# ipmi.net
KiCad netlist of a schematic drawn in Altium Designer
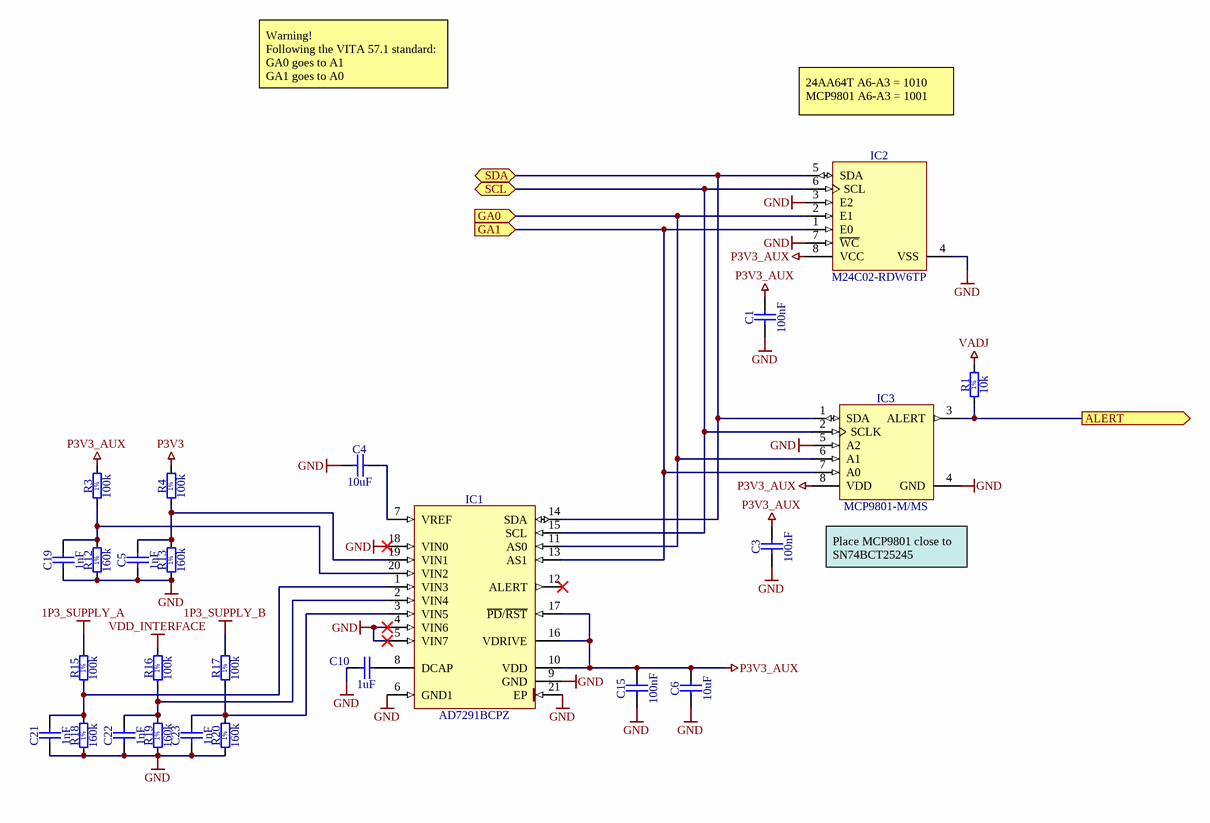
[diagram p0: ipmi.SchDoc]

(export (version "E")
  (design (tool "Eeschema 10.0.6"))
  (components
    (comp (ref "C1")
      (value "100nF")
      (footprint "CAPC1005X55N")
      (description "Non-polarised capacitor")
      (fields
        (field (name "PART NUMBER") "CC0402_100NF_16V_10%_X7R")
        (field (name "VOLTAGE") "16V")
        (field (name "AUTHOR") "CERN DEM JLC")
      )
      (libsource (lib "Capacitors") (part "Capacitor - non polarized"))
    )
    (comp (ref "C3")
      (value "100nF")
      (footprint "CAPC1005X55N")
      (description "Non-polarised capacitor")
      (fields
        (field (name "PART NUMBER") "CC0402_100NF_16V_10%_X7R")
        (field (name "VOLTAGE") "16V")
        (field (name "AUTHOR") "CERN DEM JLC")
      )
      (libsource (lib "Capacitors") (part "Capacitor - non polarized"))
    )
    (comp (ref "C4")
      (value "10uF")
      (footprint "CAPC1608X87N")
      (description "Non-polarised capacitor")
      (fields
        (field (name "PART NUMBER") "CC0603_10UF_6.3V_20%_X5R")
        (field (name "VOLTAGE") "6.3V")
        (field (name "AUTHOR") "CERN DEM JLC")
      )
      (libsource (lib "Capacitors") (part "Capacitor - non polarized"))
    )
    (comp (ref "C5")
      (value "1nF")
      (footprint "CAPC1005X55N")
      (description "Non-polarised capacitor")
      (fields
        (field (name "PART NUMBER") "CC0402_1NF_50V_10%_X7R")
        (field (name "VOLTAGE") "50V")
        (field (name "AUTHOR") "CERN DEM JLC")
      )
      (libsource (lib "Capacitors") (part "Capacitor - non polarized"))
    )
    (comp (ref "C6")
      (value "10uF")
      (footprint "CAPC1608X87N")
      (description "Non-polarised capacitor")
      (fields
        (field (name "PART NUMBER") "CC0603_10UF_6.3V_20%_X5R")
        (field (name "VOLTAGE") "6.3V")
        (field (name "AUTHOR") "CERN DEM JLC")
      )
      (libsource (lib "Capacitors") (part "Capacitor - non polarized"))
    )
    (comp (ref "C10")
      (value "1uF")
      (footprint "CAPC1608X87N")
      (description "Non-polarised capacitor")
      (fields
        (field (name "PART NUMBER") "CC0603_1UF_16V_10%_X7R")
        (field (name "VOLTAGE") "16V")
        (field (name "AUTHOR") "CERN DEM JLC")
      )
      (libsource (lib "Capacitors") (part "Capacitor - non polarized"))
    )
    (comp (ref "C15")
      (value "100nF")
      (footprint "CAPC1005X55N")
      (description "Non-polarised capacitor")
      (fields
        (field (name "PART NUMBER") "CC0402_100NF_16V_10%_X7R")
        (field (name "VOLTAGE") "16V")
        (field (name "AUTHOR") "CERN DEM JLC")
      )
      (libsource (lib "Capacitors") (part "Capacitor - non polarized"))
    )
    (comp (ref "C19")
      (value "1nF")
      (footprint "CAPC1005X55N")
      (description "Non-polarised capacitor")
      (fields
        (field (name "PART NUMBER") "CC0402_1NF_50V_10%_X7R")
        (field (name "VOLTAGE") "50V")
        (field (name "AUTHOR") "CERN DEM JLC")
      )
      (libsource (lib "Capacitors") (part "Capacitor - non polarized"))
    )
    (comp (ref "C21")
      (value "1nF")
      (footprint "CAPC1005X55N")
      (description "Non-polarised capacitor")
      (fields
        (field (name "PART NUMBER") "CC0402_1NF_50V_10%_X7R")
        (field (name "VOLTAGE") "50V")
        (field (name "AUTHOR") "CERN DEM JLC")
      )
      (libsource (lib "Capacitors") (part "Capacitor - non polarized"))
    )
    (comp (ref "C22")
      (value "1nF")
      (footprint "CAPC1005X55N")
      (description "Non-polarised capacitor")
      (fields
        (field (name "PART NUMBER") "CC0402_1NF_50V_10%_X7R")
        (field (name "VOLTAGE") "50V")
        (field (name "AUTHOR") "CERN DEM JLC")
      )
      (libsource (lib "Capacitors") (part "Capacitor - non polarized"))
    )
    (comp (ref "C23")
      (value "1nF")
      (footprint "CAPC1005X55N")
      (description "Non-polarised capacitor")
      (fields
        (field (name "PART NUMBER") "CC0402_1NF_50V_10%_X7R")
        (field (name "VOLTAGE") "50V")
        (field (name "AUTHOR") "CERN DEM JLC")
      )
      (libsource (lib "Capacitors") (part "Capacitor - non polarized"))
    )
    (comp (ref "IC1")
      (value "AD7291BCPZ")
      (footprint "QFN50P400X400X80-21N-S275")
      (description "8-Channel, I2C, 12-Bit SAR ADC with Temperature Sensor")
      (fields (field (name "MANUFACTURER") "ANALOG DEVICES") (field (name "AUTHOR") "CERN DEM JLC"))
      (libsource (lib "ICs And Semiconductors") (part "AD7291"))
    )
    (comp (ref "IC2")
      (value "M24C02-RDW6TP")
      (footprint "SOP65P640X120-8N")
      (description "2-Kbit (256 x 8bit) Serial I2C Bus EEPROM")
      (fields (field (name "MANUFACTURER") "ST MICROELECTRONICS") (field (name "AUTHOR") "CERN DEM JLC"))
      (libsource (lib "ICs And Semiconductors") (part "M24C02‐RDW"))
    )
    (comp (ref "IC3")
      (value "MCP9801-M/MS")
      (footprint "SOP65P490X110-8N")
      (description "2-Wire High-Accuracy Temperature Sensor")
      (fields (field (name "MANUFACTURER") "MICROCHIP TECHNOLOGIY") (field (name "AUTHOR") "CERN DEM JLC"))
      (libsource (lib "ICs And Semiconductors") (part "MCP9801-M/MS"))
    )
    (comp (ref "R1")
      (value "10k")
      (footprint "RESC1005X40N")
      (description "Resistor - 1%")
      (fields
        (field (name "PART NUMBER") "R0402_10K_1%_0.0625W_100PPM")
        (field (name "POWER") "0.0625W")
        (field (name "AUTHOR") "CERN DEM JLC")
      )
      (libsource (lib "Resistors") (part "Resistor - 1%"))
    )
    (comp (ref "R3")
      (value "100k")
      (footprint "RESC1005X40N")
      (description "Resistor - 1%")
      (fields
        (field (name "PART NUMBER") "R0402_100K_1%_0.0625W_100PPM")
        (field (name "POWER") "0.0625W")
        (field (name "AUTHOR") "CERN DEM JLC")
      )
      (libsource (lib "Resistors") (part "Resistor - 1%"))
    )
    (comp (ref "R4")
      (value "100k")
      (footprint "RESC1005X40N")
      (description "Resistor - 1%")
      (fields
        (field (name "PART NUMBER") "R0402_100K_1%_0.0625W_100PPM")
        (field (name "POWER") "0.0625W")
        (field (name "AUTHOR") "CERN DEM JLC")
      )
      (libsource (lib "Resistors") (part "Resistor - 1%"))
    )
    (comp (ref "R12")
      (value "160k")
      (footprint "RESC1005X40N")
      (description "Resistor - 1%")
      (fields
        (field (name "PART NUMBER") "R0402_160K_1%_0.0625W_100PPM")
        (field (name "POWER") "0.0625W")
        (field (name "AUTHOR") "CERN DEM JLC")
      )
      (libsource (lib "Resistors") (part "Resistor - 1%"))
    )
    (comp (ref "R13")
      (value "160k")
      (footprint "RESC1005X40N")
      (description "Resistor - 1%")
      (fields
        (field (name "PART NUMBER") "R0402_160K_1%_0.0625W_100PPM")
        (field (name "POWER") "0.0625W")
        (field (name "AUTHOR") "CERN DEM JLC")
      )
      (libsource (lib "Resistors") (part "Resistor - 1%"))
    )
    (comp (ref "R15")
      (value "100k")
      (footprint "RESC1005X40N")
      (description "Resistor - 1%")
      (fields
        (field (name "PART NUMBER") "R0402_100K_1%_0.0625W_100PPM")
        (field (name "POWER") "0.0625W")
        (field (name "AUTHOR") "CERN DEM JLC")
      )
      (libsource (lib "Resistors") (part "Resistor - 1%"))
    )
    (comp (ref "R16")
      (value "100k")
      (footprint "RESC1005X40N")
      (description "Resistor - 1%")
      (fields
        (field (name "PART NUMBER") "R0402_100K_1%_0.0625W_100PPM")
        (field (name "POWER") "0.0625W")
        (field (name "AUTHOR") "CERN DEM JLC")
      )
      (libsource (lib "Resistors") (part "Resistor - 1%"))
    )
    (comp (ref "R17")
      (value "100k")
      (footprint "RESC1005X40N")
      (description "Resistor - 1%")
      (fields
        (field (name "PART NUMBER") "R0402_100K_1%_0.0625W_100PPM")
        (field (name "POWER") "0.0625W")
        (field (name "AUTHOR") "CERN DEM JLC")
      )
      (libsource (lib "Resistors") (part "Resistor - 1%"))
    )
    (comp (ref "R18")
      (value "160k")
      (footprint "RESC1005X40N")
      (description "Resistor - 1%")
      (fields
        (field (name "PART NUMBER") "R0402_160K_1%_0.0625W_100PPM")
        (field (name "POWER") "0.0625W")
        (field (name "AUTHOR") "CERN DEM JLC")
      )
      (libsource (lib "Resistors") (part "Resistor - 1%"))
    )
    (comp (ref "R19")
      (value "160k")
      (footprint "RESC1005X40N")
      (description "Resistor - 1%")
      (fields
        (field (name "PART NUMBER") "R0402_160K_1%_0.0625W_100PPM")
        (field (name "POWER") "0.0625W")
        (field (name "AUTHOR") "CERN DEM JLC")
      )
      (libsource (lib "Resistors") (part "Resistor - 1%"))
    )
    (comp (ref "R20")
      (value "160k")
      (footprint "RESC1005X40N")
      (description "Resistor - 1%")
      (fields
        (field (name "PART NUMBER") "R0402_160K_1%_0.0625W_100PPM")
        (field (name "POWER") "0.0625W")
        (field (name "AUTHOR") "CERN DEM JLC")
      )
      (libsource (lib "Resistors") (part "Resistor - 1%"))
    )
  )
  (nets
    (net (code "1") (name "/ALERT") (class "Default")
      (node (ref "IC3") (pin "3") (pinfunction "ALERT_3") (pintype "output"))
      (node (ref "R1") (pin "1") (pinfunction "1_1") (pintype "passive"))
    )
    (net (code "2") (name "/GA0") (class "Default")
      (node (ref "IC1") (pin "11") (pinfunction "AS0_11") (pintype "input"))
      (node (ref "IC2") (pin "2") (pinfunction "E1_2") (pintype "input"))
      (node (ref "IC3") (pin "6") (pinfunction "A1_6") (pintype "input"))
    )
    (net (code "3") (name "/GA1") (class "Default")
      (node (ref "IC1") (pin "13") (pinfunction "AS1_13") (pintype "input"))
      (node (ref "IC2") (pin "1") (pinfunction "E0_1") (pintype "input"))
      (node (ref "IC3") (pin "7") (pinfunction "A0_7") (pintype "input"))
    )
    (net (code "4") (name "/SCL") (class "Default")
      (node (ref "IC1") (pin "15") (pinfunction "SCL_15") (pintype "input"))
      (node (ref "IC2") (pin "6") (pinfunction "SCL_6") (pintype "input"))
      (node (ref "IC3") (pin "2") (pinfunction "SCLK_2") (pintype "input"))
    )
    (net (code "5") (name "/SDA") (class "Default")
      (node (ref "IC1") (pin "14") (pinfunction "SDA_14") (pintype "bidirectional"))
      (node (ref "IC2") (pin "5") (pinfunction "SDA_5") (pintype "bidirectional"))
      (node (ref "IC3") (pin "1") (pinfunction "SDA_1") (pintype "bidirectional"))
    )
    (net (code "6") (name "1P3_SUPPLY_A") (class "Default")
      (node (ref "R15") (pin "2") (pinfunction "2_2") (pintype "passive"))
    )
    (net (code "7") (name "1P3_SUPPLY_B") (class "Default")
      (node (ref "R17") (pin "2") (pinfunction "2_2") (pintype "passive"))
    )
    (net (code "8") (name "GND") (class "Default")
      (node (ref "C1") (pin "1") (pinfunction "1_1") (pintype "passive"))
      (node (ref "C10") (pin "1") (pinfunction "1_1") (pintype "passive"))
      (node (ref "C15") (pin "1") (pinfunction "1_1") (pintype "passive"))
      (node (ref "C19") (pin "1") (pinfunction "1_1") (pintype "passive"))
      (node (ref "C21") (pin "1") (pinfunction "1_1") (pintype "passive"))
      (node (ref "C22") (pin "1") (pinfunction "1_1") (pintype "passive"))
      (node (ref "C23") (pin "1") (pinfunction "1_1") (pintype "passive"))
      (node (ref "C3") (pin "1") (pinfunction "1_1") (pintype "passive"))
      (node (ref "C4") (pin "1") (pinfunction "1_1") (pintype "passive"))
      (node (ref "C5") (pin "1") (pinfunction "1_1") (pintype "passive"))
      (node (ref "C6") (pin "1") (pinfunction "1_1") (pintype "passive"))
      (node (ref "IC1") (pin "18") (pinfunction "VIN0_18") (pintype "input"))
      (node (ref "IC1") (pin "21") (pinfunction "EP_21") (pintype "input"))
      (node (ref "IC1") (pin "4") (pinfunction "VIN6_4") (pintype "input"))
      (node (ref "IC1") (pin "5") (pinfunction "VIN7_5") (pintype "input"))
      (node (ref "IC1") (pin "6") (pinfunction "GND1_6") (pintype "input"))
      (node (ref "IC1") (pin "9") (pinfunction "GND_9") (pintype "power_in"))
      (node (ref "IC2") (pin "3") (pinfunction "E2_3") (pintype "input"))
      (node (ref "IC2") (pin "4") (pinfunction "VSS_4") (pintype "power_in"))
      (node (ref "IC2") (pin "7") (pinfunction "~{WC}_7") (pintype "input"))
      (node (ref "IC3") (pin "4") (pinfunction "GND_4") (pintype "power_in"))
      (node (ref "IC3") (pin "5") (pinfunction "A2_5") (pintype "input"))
      (node (ref "R12") (pin "1") (pinfunction "1_1") (pintype "passive"))
      (node (ref "R13") (pin "1") (pinfunction "1_1") (pintype "passive"))
      (node (ref "R18") (pin "1") (pinfunction "1_1") (pintype "passive"))
      (node (ref "R19") (pin "1") (pinfunction "1_1") (pintype "passive"))
      (node (ref "R20") (pin "1") (pinfunction "1_1") (pintype "passive"))
    )
    (net (code "9") (name "Net-(IC1-DCAP)") (class "Default")
      (node (ref "C10") (pin "2") (pinfunction "2_2") (pintype "passive"))
      (node (ref "IC1") (pin "8") (pinfunction "DCAP_8") (pintype "passive"))
    )
    (net (code "10") (name "Net-(IC1-VIN1)") (class "Default")
      (node (ref "C5") (pin "2") (pinfunction "2_2") (pintype "passive"))
      (node (ref "IC1") (pin "19") (pinfunction "VIN1_19") (pintype "input"))
      (node (ref "R13") (pin "2") (pinfunction "2_2") (pintype "passive"))
      (node (ref "R4") (pin "1") (pinfunction "1_1") (pintype "passive"))
    )
    (net (code "11") (name "Net-(IC1-VIN2)") (class "Default")
      (node (ref "C19") (pin "2") (pinfunction "2_2") (pintype "passive"))
      (node (ref "IC1") (pin "20") (pinfunction "VIN2_20") (pintype "input"))
      (node (ref "R12") (pin "2") (pinfunction "2_2") (pintype "passive"))
      (node (ref "R3") (pin "1") (pinfunction "1_1") (pintype "passive"))
    )
    (net (code "12") (name "Net-(IC1-VIN3)") (class "Default")
      (node (ref "C21") (pin "2") (pinfunction "2_2") (pintype "passive"))
      (node (ref "IC1") (pin "1") (pinfunction "VIN3_1") (pintype "input"))
      (node (ref "R15") (pin "1") (pinfunction "1_1") (pintype "passive"))
      (node (ref "R18") (pin "2") (pinfunction "2_2") (pintype "passive"))
    )
    (net (code "13") (name "Net-(IC1-VIN4)") (class "Default")
      (node (ref "C22") (pin "2") (pinfunction "2_2") (pintype "passive"))
      (node (ref "IC1") (pin "2") (pinfunction "VIN4_2") (pintype "input"))
      (node (ref "R16") (pin "1") (pinfunction "1_1") (pintype "passive"))
      (node (ref "R19") (pin "2") (pinfunction "2_2") (pintype "passive"))
    )
    (net (code "14") (name "Net-(IC1-VIN5)") (class "Default")
      (node (ref "C23") (pin "2") (pinfunction "2_2") (pintype "passive"))
      (node (ref "IC1") (pin "3") (pinfunction "VIN5_3") (pintype "input"))
      (node (ref "R17") (pin "1") (pinfunction "1_1") (pintype "passive"))
      (node (ref "R20") (pin "2") (pinfunction "2_2") (pintype "passive"))
    )
    (net (code "15") (name "Net-(IC1-VREF)") (class "Default")
      (node (ref "C4") (pin "2") (pinfunction "2_2") (pintype "passive"))
      (node (ref "IC1") (pin "7") (pinfunction "VREF_7") (pintype "input"))
    )
    (net (code "16") (name "P3V3") (class "Default")
      (node (ref "R4") (pin "2") (pinfunction "2_2") (pintype "passive"))
    )
    (net (code "17") (name "P3V3_AUX") (class "Default")
      (node (ref "C1") (pin "2") (pinfunction "2_2") (pintype "passive"))
      (node (ref "C15") (pin "2") (pinfunction "2_2") (pintype "passive"))
      (node (ref "C3") (pin "2") (pinfunction "2_2") (pintype "passive"))
      (node (ref "C6") (pin "2") (pinfunction "2_2") (pintype "passive"))
      (node (ref "IC1") (pin "10") (pinfunction "VDD_10") (pintype "power_in"))
      (node (ref "IC1") (pin "16") (pinfunction "VDRIVE_16") (pintype "power_in"))
      (node (ref "IC1") (pin "17") (pinfunction "~{PD}/~{RST}_17") (pintype "input"))
      (node (ref "IC2") (pin "8") (pinfunction "VCC_8") (pintype "power_in"))
      (node (ref "IC3") (pin "8") (pinfunction "VDD_8") (pintype "power_in"))
      (node (ref "R3") (pin "2") (pinfunction "2_2") (pintype "passive"))
    )
    (net (code "18") (name "VADJ") (class "Default")
      (node (ref "R1") (pin "2") (pinfunction "2_2") (pintype "passive"))
    )
    (net (code "19") (name "VDD_INTERFACE") (class "Default")
      (node (ref "R16") (pin "2") (pinfunction "2_2") (pintype "passive"))
    )
    (net (code "20") (name "unconnected-(IC1-ALERT-Pad12)") (class "Default")
      (node (ref "IC1") (pin "12") (pinfunction "ALERT_12") (pintype "output+no_connect"))
    )
  )
)
